# node_captor_piezo.net
KiCad netlist of a schematic drawn in EAGLE
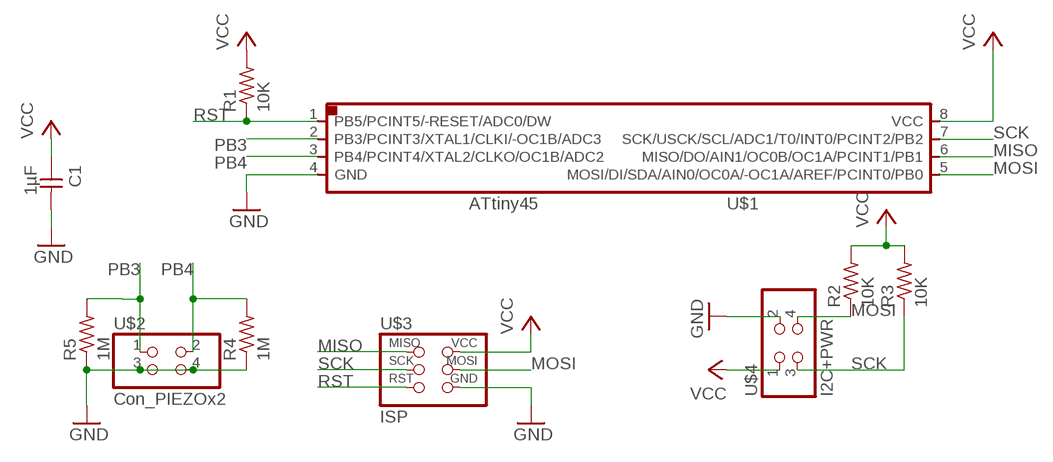
[diagram p0: schematic, sheet 1]

(export (version "E")
  (design (tool "Eeschema 10.0.6"))
  (components
    (comp (ref "C1")
      (value "1µF")
      (footprint "eagle-import:C1206FAB")
      (libsource (lib "eagle-import") (part "CAP-UNPOLARIZEDFAB"))
    )
    (comp (ref "R1")
      (value "10K")
      (footprint "eagle-import:R1206FAB")
      (libsource (lib "eagle-import") (part "RES-US1206FAB"))
    )
    (comp (ref "R2")
      (value "10K")
      (footprint "eagle-import:R1206FAB")
      (libsource (lib "eagle-import") (part "RES-US1206FAB"))
    )
    (comp (ref "R3")
      (value "10K")
      (footprint "eagle-import:R1206FAB")
      (libsource (lib "eagle-import") (part "RES-US1206FAB"))
    )
    (comp (ref "R4")
      (value "1M")
      (footprint "eagle-import:R1206FAB")
      (libsource (lib "eagle-import") (part "RES-US1206FAB"))
    )
    (comp (ref "R5")
      (value "1M")
      (footprint "eagle-import:R1206FAB")
      (libsource (lib "eagle-import") (part "RES-US1206FAB"))
    )
    (comp (ref "U$1")
      (value "ATTINY45SI")
      (footprint "eagle-import:SOIC8")
      (libsource (lib "eagle-import") (part "ATTINY45SI"))
    )
    (comp (ref "U$2")
      (value "Con_PIEZOx2")
      (footprint "eagle-import:2X02SMD")
      (libsource (lib "eagle-import") (part "PINHD-2X2-SMD"))
    )
    (comp (ref "U$3")
      (value "ISP")
      (footprint "eagle-import:2X03SMD")
      (libsource (lib "eagle-import") (part "AVRISPSMD"))
    )
    (comp (ref "U$4")
      (value "I2C+PWR")
      (footprint "eagle-import:2X02SMD")
      (libsource (lib "eagle-import") (part "PINHD-2X2-SMD"))
    )
  )
  (nets
    (net (code "1") (name "/MISO") (class "Default")
      (node (ref "U$1") (pin "6") (pinfunction "MISO/DO/AIN1/OC0B/OC1A/PCINT1/PB1_6") (pintype "bidirectional"))
      (node (ref "U$3") (pin "1") (pinfunction "MISO_1") (pintype "passive"))
    )
    (net (code "2") (name "/MOSI") (class "Default")
      (node (ref "R2") (pin "1") (pinfunction "1_1") (pintype "passive"))
      (node (ref "U$1") (pin "5") (pinfunction "MOSI/DI/SDA/AIN0/OC0A/-OC1A/AREF/PCINT0/PB0_5") (pintype "bidirectional"))
      (node (ref "U$3") (pin "4") (pinfunction "MOSI_4") (pintype "passive"))
      (node (ref "U$4") (pin "4") (pinfunction "4_4") (pintype "passive"))
    )
    (net (code "3") (name "/PB3") (class "Default")
      (node (ref "R5") (pin "2") (pinfunction "2_2") (pintype "passive"))
      (node (ref "U$1") (pin "2") (pinfunction "PB3/PCINT3/XTAL1/CLKI/-OC1B/ADC3_2") (pintype "bidirectional"))
      (node (ref "U$2") (pin "1") (pinfunction "1_1") (pintype "passive"))
    )
    (net (code "4") (name "/PB4") (class "Default")
      (node (ref "R4") (pin "2") (pinfunction "2_2") (pintype "passive"))
      (node (ref "U$1") (pin "3") (pinfunction "PB4/PCINT4/XTAL2/CLKO/OC1B/ADC2_3") (pintype "bidirectional"))
      (node (ref "U$2") (pin "2") (pinfunction "2_2") (pintype "passive"))
    )
    (net (code "5") (name "/RST") (class "Default")
      (node (ref "R1") (pin "1") (pinfunction "1_1") (pintype "passive"))
      (node (ref "U$1") (pin "1") (pinfunction "PB5/PCINT5/-RESET/ADC0/DW_1") (pintype "bidirectional"))
      (node (ref "U$3") (pin "5") (pinfunction "RST_5") (pintype "passive"))
    )
    (net (code "6") (name "/SCK") (class "Default")
      (node (ref "R3") (pin "1") (pinfunction "1_1") (pintype "passive"))
      (node (ref "U$1") (pin "7") (pinfunction "SCK/USCK/SCL/ADC1/T0/INT0/PCINT2/PB2_7") (pintype "bidirectional"))
      (node (ref "U$3") (pin "3") (pinfunction "SCK_3") (pintype "passive"))
      (node (ref "U$4") (pin "3") (pinfunction "3_3") (pintype "passive"))
    )
    (net (code "7") (name "GND") (class "Default")
      (node (ref "C1") (pin "2") (pinfunction "2_2") (pintype "passive"))
      (node (ref "R4") (pin "1") (pinfunction "1_1") (pintype "passive"))
      (node (ref "R5") (pin "1") (pinfunction "1_1") (pintype "passive"))
      (node (ref "U$1") (pin "4") (pinfunction "GND_4") (pintype "bidirectional"))
      (node (ref "U$2") (pin "3") (pinfunction "3_3") (pintype "passive"))
      (node (ref "U$2") (pin "4") (pinfunction "4_4") (pintype "passive"))
      (node (ref "U$3") (pin "6") (pinfunction "GND_6") (pintype "passive"))
      (node (ref "U$4") (pin "2") (pinfunction "2_2") (pintype "passive"))
    )
    (net (code "8") (name "VCC") (class "Default")
      (node (ref "C1") (pin "1") (pinfunction "1_1") (pintype "passive"))
      (node (ref "R1") (pin "2") (pinfunction "2_2") (pintype "passive"))
      (node (ref "R2") (pin "2") (pinfunction "2_2") (pintype "passive"))
      (node (ref "R3") (pin "2") (pinfunction "2_2") (pintype "passive"))
      (node (ref "U$1") (pin "8") (pinfunction "VCC_8") (pintype "bidirectional"))
      (node (ref "U$3") (pin "2") (pinfunction "VCC_2") (pintype "passive"))
      (node (ref "U$4") (pin "1") (pinfunction "1_1") (pintype "passive"))
    )
  )
)
